# Connectors.net
KiCad netlist of a schematic drawn in Altium Designer
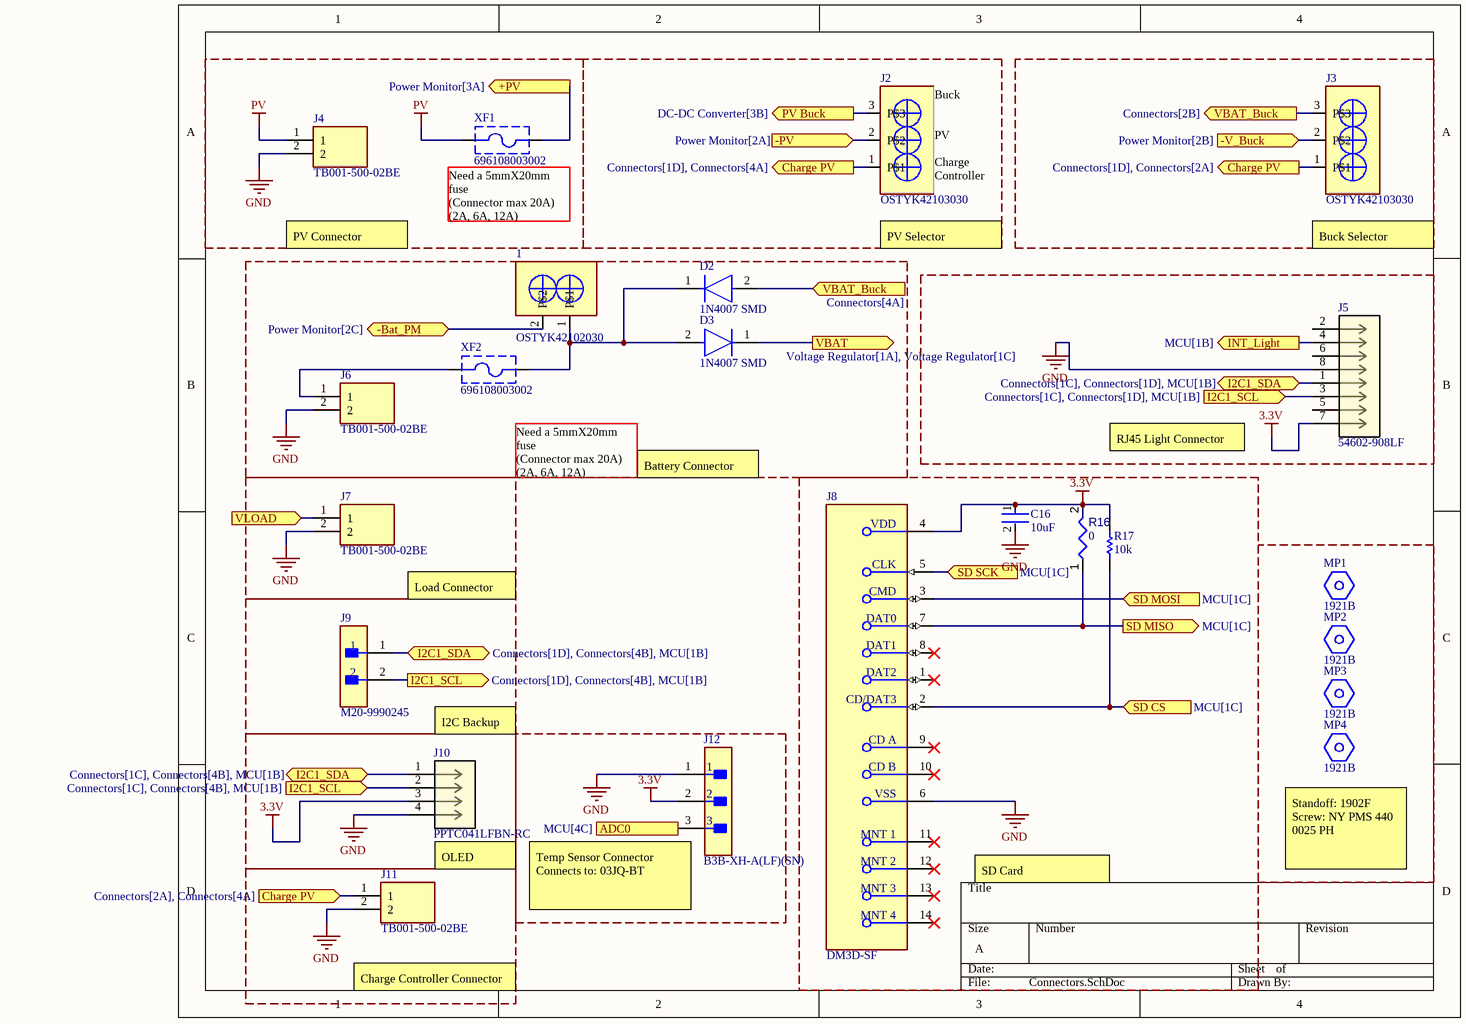
[diagram p0: Connectors.SchDoc]

(export (version "E")
  (design (tool "Eeschema 10.0.6"))
  (components
    (comp (ref "1")
      (value "OSTYK42102030")
      (footprint "OSTYK42102030")
      (description "2 Circuit 0.325 _8.26mm_ Barrier Block Connector, Screws with Captive Plate")
      (fields (field (name "MF") "On Shore"))
      (libsource (lib "OSTYK42102030") (part "OSTYK42102030"))
    )
    (comp (ref "C16")
      (value "10uF")
      (footprint "FP-GRM188-0_1-e0_2_0_55-IPC_A")
      (fields (field (name "VOLTAGE") "6.3V") (field (name "TOLERANCE") "20%"))
      (libsource (lib "Altium Content Vault") (part "02cd4be3c70576c341d710602a673aa"))
    )
    (comp (ref "D2")
      (value "1N4007 SMD")
      (footprint "FP-1N4007_SMD-IPC_C")
      (description "Rectifier, 1Kv, 1A, Do-214Ac Rohs Compliant: Yes")
      (libsource (lib "Altium Content Vault") (part "d7152d700b627762746794eb795d46e"))
    )
    (comp (ref "D3")
      (value "1N4007 SMD")
      (footprint "FP-1N4007_SMD-IPC_C")
      (description "Rectifier, 1Kv, 1A, Do-214Ac Rohs Compliant: Yes")
      (libsource (lib "Altium Content Vault") (part "d7152d700b627762746794eb795d46e"))
    )
    (comp (ref "J2")
      (value "OSTYK42103030")
      (footprint "OSTYK42103030")
      (description "3 Circuit 0.325 (8.26mm) Barrier Block Connector, Screws with Captive Plate")
      (fields (field (name "MF") "On Shore"))
      (libsource (lib "WPI High Power Rocketry Club") (part "OSTYK42103030"))
    )
    (comp (ref "J3")
      (value "OSTYK42103030")
      (footprint "OSTYK42103030")
      (description "3 Circuit 0.325 (8.26mm) Barrier Block Connector, Screws with Captive Plate")
      (fields (field (name "MF") "On Shore"))
      (libsource (lib "WPI High Power Rocketry Club") (part "OSTYK42103030"))
    )
    (comp (ref "J4")
      (value "TB001-500-02BE")
      (footprint "CUI_TB001-500-02BE")
      (description "2~24 Poles, Screw Type, Horizontal, 5.0 Pitch, 22~12 (AWG), Terminal Block Connector")
      (fields (field (name "MF") "CUI Devices") (field (name "DIGI-KEY_PART_NUMBER") "102-6134-ND"))
      (libsource (lib "TB001-500-02BE") (part "TB001-500-02BE"))
    )
    (comp (ref "J5")
      (value "54602-908LF")
      (footprint "CONN8_2-908LF_AMP")
      (description "No Description Available")
      (libsource (lib "54602-908LF") (part "54602-908LF"))
    )
    (comp (ref "J6")
      (value "TB001-500-02BE")
      (footprint "CUI_TB001-500-02BE")
      (description "2~24 Poles, Screw Type, Horizontal, 5.0 Pitch, 22~12 (AWG), Terminal Block Connector")
      (fields (field (name "MF") "CUI Devices") (field (name "DIGI-KEY_PART_NUMBER") "102-6134-ND"))
      (libsource (lib "TB001-500-02BE") (part "TB001-500-02BE"))
    )
    (comp (ref "J7")
      (value "TB001-500-02BE")
      (footprint "CUI_TB001-500-02BE")
      (description "2~24 Poles, Screw Type, Horizontal, 5.0 Pitch, 22~12 (AWG), Terminal Block Connector")
      (fields (field (name "MF") "CUI Devices") (field (name "DIGI-KEY_PART_NUMBER") "102-6134-ND"))
      (libsource (lib "TB001-500-02BE") (part "TB001-500-02BE"))
    )
    (comp (ref "J8")
      (value "DM3D-SF")
      (footprint "FP-DM3D-SF-MFG")
      (description "CONN MICRO SD CARD PUSH-PULL")
      (libsource (lib "Altium Content Vault") (part "375756fe1061de806c40c19e9001ea3"))
    )
    (comp (ref "J9")
      (value "M20-9990245")
      (footprint "FP-M20-9990245-MFG")
      (description "CONN HEADER VERT 2POS 2.54MM")
      (fields (field (name "VOLTAGE") "50V"))
      (libsource (lib "Altium Content Vault") (part "3bc925449376181038e59eaffc5286c"))
    )
    (comp (ref "J10")
      (value "PPTC041LFBN-RC")
      (footprint "CONN_PPTC041LFBN-RC_SUL")
      (description "No Description Available")
      (libsource (lib "PPTC041LFBN-RC") (part "PPTC041LFBN-RC"))
    )
    (comp (ref "J11")
      (value "TB001-500-02BE")
      (footprint "CUI_TB001-500-02BE")
      (description "2~24 Poles, Screw Type, Horizontal, 5.0 Pitch, 22~12 (AWG), Terminal Block Connector")
      (fields (field (name "MF") "CUI Devices") (field (name "DIGI-KEY_PART_NUMBER") "102-6134-ND"))
      (libsource (lib "TB001-500-02BE") (part "TB001-500-02BE"))
    )
    (comp (ref "J12")
      (value "B3B-XH-A(LF)(SN)")
      (footprint "FP-B3B-XH-A_LF_SN-MFG")
      (description "CONN HEADER VERT 3POS 2.5MM")
      (libsource (lib "Altium Content Vault") (part "0d3f023dd272f625e17a2be33dea85f"))
    )
    (comp (ref "MP1")
      (value "1921B")
      (footprint "FP-1921B-MFG")
      (description "1921B Standoff, 1/4 Hex, Female, Threaded 4-40, Length .500, Stainless Steel")
      (libsource (lib "Altium Content Vault") (part "08a03163f22740170b61ca9211e1d1e"))
    )
    (comp (ref "MP2")
      (value "1921B")
      (footprint "FP-1921B-MFG")
      (description "1921B Standoff, 1/4 Hex, Female, Threaded 4-40, Length .500, Stainless Steel")
      (libsource (lib "Altium Content Vault") (part "08a03163f22740170b61ca9211e1d1e"))
    )
    (comp (ref "MP3")
      (value "1921B")
      (footprint "FP-1921B-MFG")
      (description "1921B Standoff, 1/4 Hex, Female, Threaded 4-40, Length .500, Stainless Steel")
      (libsource (lib "Altium Content Vault") (part "08a03163f22740170b61ca9211e1d1e"))
    )
    (comp (ref "MP4")
      (value "1921B")
      (footprint "FP-1921B-MFG")
      (description "1921B Standoff, 1/4 Hex, Female, Threaded 4-40, Length .500, Stainless Steel")
      (libsource (lib "Altium Content Vault") (part "08a03163f22740170b61ca9211e1d1e"))
    )
    (comp (ref "R16")
      (value "0")
      (footprint "RESC0603(1608)_L")
      (description "Jumper 0603 (1608 Metric)")
      (fields (field (name "Comment") "0R3J"))
      (libsource (lib "WPI High Power Rocketry Club") (part "0R3J"))
    )
    (comp (ref "R17")
      (value "10k")
      (footprint "RESC1609X50X30NL8T20")
      (description "Chip Resistor, 10 KOhm, +/- 1%, 100 mW, -55 to 155 degC, 0603 (1608 Metric), RoHS, Tape and Reel")
      (fields (field (name "MANUFACTURER") "Vishay Semiconductor"))
      (libsource (lib "Altium Content Vault") (part "RES-2"))
    )
    (comp (ref "XF1")
      (value "696108003002")
      (footprint "696108003002")
      (libsource (lib "Altium Content Vault") (part "Fuse Holder"))
    )
    (comp (ref "XF2")
      (value "696108003002")
      (footprint "696108003002")
      (libsource (lib "Altium Content Vault") (part "Fuse Holder"))
    )
  )
  (nets
    (net (code "1") (name "/+PV") (class "Default")
      (node (ref "XF1") (pin "2") (pinfunction "2_2") (pintype "passive"))
    )
    (net (code "2") (name "/-Bat_PM") (class "Default")
      (node (ref "1") (pin "2") (pinfunction "P$2_2") (pintype "bidirectional"))
    )
    (net (code "3") (name "/-PV") (class "Default")
      (node (ref "J2") (pin "2") (pinfunction "P$2_2") (pintype "bidirectional"))
    )
    (net (code "4") (name "/-V_Buck") (class "Default")
      (node (ref "J3") (pin "2") (pinfunction "P$2_2") (pintype "bidirectional"))
    )
    (net (code "5") (name "/ADC0") (class "Default")
      (node (ref "J12") (pin "3") (pinfunction "3_3") (pintype "passive"))
    )
    (net (code "6") (name "/Charge PV") (class "Default")
      (node (ref "J11") (pin "1") (pinfunction "1_1") (pintype "passive"))
      (node (ref "J2") (pin "1") (pinfunction "P$1_1") (pintype "bidirectional"))
      (node (ref "J3") (pin "1") (pinfunction "P$1_1") (pintype "bidirectional"))
    )
    (net (code "7") (name "/I2C1_SCL") (class "Default")
      (node (ref "J10") (pin "2") (pinfunction "2_2") (pintype "passive"))
      (node (ref "J5") (pin "3") (pinfunction "3_3") (pintype "passive"))
      (node (ref "J9") (pin "2") (pinfunction "2_2") (pintype "passive"))
    )
    (net (code "8") (name "/I2C1_SDA") (class "Default")
      (node (ref "J10") (pin "1") (pinfunction "1_1") (pintype "passive"))
      (node (ref "J5") (pin "1") (pinfunction "1_1") (pintype "passive"))
      (node (ref "J9") (pin "1") (pinfunction "1_1") (pintype "passive"))
    )
    (net (code "9") (name "/INT_Light") (class "Default")
      (node (ref "J5") (pin "4") (pinfunction "4_4") (pintype "passive"))
    )
    (net (code "10") (name "/PV Buck") (class "Default")
      (node (ref "J2") (pin "3") (pinfunction "P$3_3") (pintype "bidirectional"))
    )
    (net (code "11") (name "/SD CS") (class "Default")
      (node (ref "J8") (pin "2") (pinfunction "CD/DAT3_2") (pintype "bidirectional"))
      (node (ref "R17") (pin "1") (pinfunction "1_1") (pintype "passive"))
    )
    (net (code "12") (name "/SD MISO") (class "Default")
      (node (ref "J8") (pin "7") (pinfunction "DAT0_7") (pintype "bidirectional"))
      (node (ref "R16") (pin "1") (pinfunction "1_1") (pintype "passive"))
    )
    (net (code "13") (name "/SD MOSI") (class "Default")
      (node (ref "J8") (pin "3") (pinfunction "CMD_3") (pintype "bidirectional"))
    )
    (net (code "14") (name "/SD SCK") (class "Default")
      (node (ref "J8") (pin "5") (pinfunction "CLK_5") (pintype "input"))
    )
    (net (code "15") (name "/VBAT") (class "Default")
      (node (ref "D3") (pin "1") (pinfunction "C_1") (pintype "passive"))
    )
    (net (code "16") (name "/VBAT_Buck") (class "Default")
      (node (ref "D2") (pin "2") (pinfunction "A_2") (pintype "passive"))
      (node (ref "J3") (pin "3") (pinfunction "P$3_3") (pintype "bidirectional"))
    )
    (net (code "17") (name "/VLOAD") (class "Default")
      (node (ref "J7") (pin "1") (pinfunction "1_1") (pintype "passive"))
    )
    (net (code "18") (name "3.3V") (class "Default")
      (node (ref "C16") (pin "1") (pinfunction "1_1") (pintype "passive"))
      (node (ref "J10") (pin "3") (pinfunction "3_3") (pintype "passive"))
      (node (ref "J12") (pin "2") (pinfunction "2_2") (pintype "passive"))
      (node (ref "J5") (pin "7") (pinfunction "7_7") (pintype "passive"))
      (node (ref "J8") (pin "4") (pinfunction "VDD_4") (pintype "power_in"))
      (node (ref "R16") (pin "2") (pinfunction "2_2") (pintype "passive"))
      (node (ref "R17") (pin "2") (pinfunction "2_2") (pintype "passive"))
    )
    (net (code "19") (name "GND") (class "Default")
      (node (ref "C16") (pin "2") (pinfunction "2_2") (pintype "passive"))
      (node (ref "J10") (pin "4") (pinfunction "4_4") (pintype "passive"))
      (node (ref "J11") (pin "2") (pinfunction "2_2") (pintype "passive"))
      (node (ref "J12") (pin "1") (pinfunction "1_1") (pintype "passive"))
      (node (ref "J4") (pin "2") (pinfunction "2_2") (pintype "passive"))
      (node (ref "J5") (pin "8") (pinfunction "8_8") (pintype "passive"))
      (node (ref "J6") (pin "2") (pinfunction "2_2") (pintype "passive"))
      (node (ref "J7") (pin "2") (pinfunction "2_2") (pintype "passive"))
      (node (ref "J8") (pin "6") (pinfunction "VSS_6") (pintype "power_in"))
    )
    (net (code "20") (name "Net-(1-P$1)") (class "Default")
      (node (ref "1") (pin "1") (pinfunction "P$1_1") (pintype "bidirectional"))
      (node (ref "D2") (pin "1") (pinfunction "C_1") (pintype "passive"))
      (node (ref "D3") (pin "2") (pinfunction "A_2") (pintype "passive"))
      (node (ref "XF2") (pin "2") (pinfunction "2_2") (pintype "passive"))
    )
    (net (code "21") (name "Net-(J6-Pad1)") (class "Default")
      (node (ref "J6") (pin "1") (pinfunction "1_1") (pintype "passive"))
      (node (ref "XF2") (pin "1") (pinfunction "1_1") (pintype "passive"))
    )
    (net (code "22") (name "PV") (class "Default")
      (node (ref "J4") (pin "1") (pinfunction "1_1") (pintype "passive"))
      (node (ref "XF1") (pin "1") (pinfunction "1_1") (pintype "passive"))
    )
    (net (code "23") (name "unconnected-(J5-Pad2)") (class "Default")
      (node (ref "J5") (pin "2") (pinfunction "2_2") (pintype "passive"))
    )
    (net (code "24") (name "unconnected-(J5-Pad5)") (class "Default")
      (node (ref "J5") (pin "5") (pinfunction "5_5") (pintype "passive"))
    )
    (net (code "25") (name "unconnected-(J5-Pad6)") (class "Default")
      (node (ref "J5") (pin "6") (pinfunction "6_6") (pintype "passive"))
    )
    (net (code "26") (name "unconnected-(J8-CD_A-Pad9)") (class "Default")
      (node (ref "J8") (pin "9") (pinfunction "CD_A_9") (pintype "passive+no_connect"))
    )
    (net (code "27") (name "unconnected-(J8-CD_B-Pad10)") (class "Default")
      (node (ref "J8") (pin "10") (pinfunction "CD_B_10") (pintype "passive+no_connect"))
    )
    (net (code "28") (name "unconnected-(J8-DAT1-Pad8)") (class "Default")
      (node (ref "J8") (pin "8") (pinfunction "DAT1_8") (pintype "bidirectional+no_connect"))
    )
    (net (code "29") (name "unconnected-(J8-DAT2-Pad1)") (class "Default")
      (node (ref "J8") (pin "1") (pinfunction "DAT2_1") (pintype "bidirectional+no_connect"))
    )
    (net (code "30") (name "unconnected-(J8-MNT_1-Pad11)") (class "Default")
      (node (ref "J8") (pin "11") (pinfunction "MNT_1_11") (pintype "passive+no_connect"))
    )
    (net (code "31") (name "unconnected-(J8-MNT_2-Pad12)") (class "Default")
      (node (ref "J8") (pin "12") (pinfunction "MNT_2_12") (pintype "passive+no_connect"))
    )
    (net (code "32") (name "unconnected-(J8-MNT_3-Pad13)") (class "Default")
      (node (ref "J8") (pin "13") (pinfunction "MNT_3_13") (pintype "passive+no_connect"))
    )
    (net (code "33") (name "unconnected-(J8-MNT_4-Pad14)") (class "Default")
      (node (ref "J8") (pin "14") (pinfunction "MNT_4_14") (pintype "passive+no_connect"))
    )
  )
)
